# 16_-_PWR_2V5_1V5.net
KiCad netlist of a schematic drawn in Altium Designer
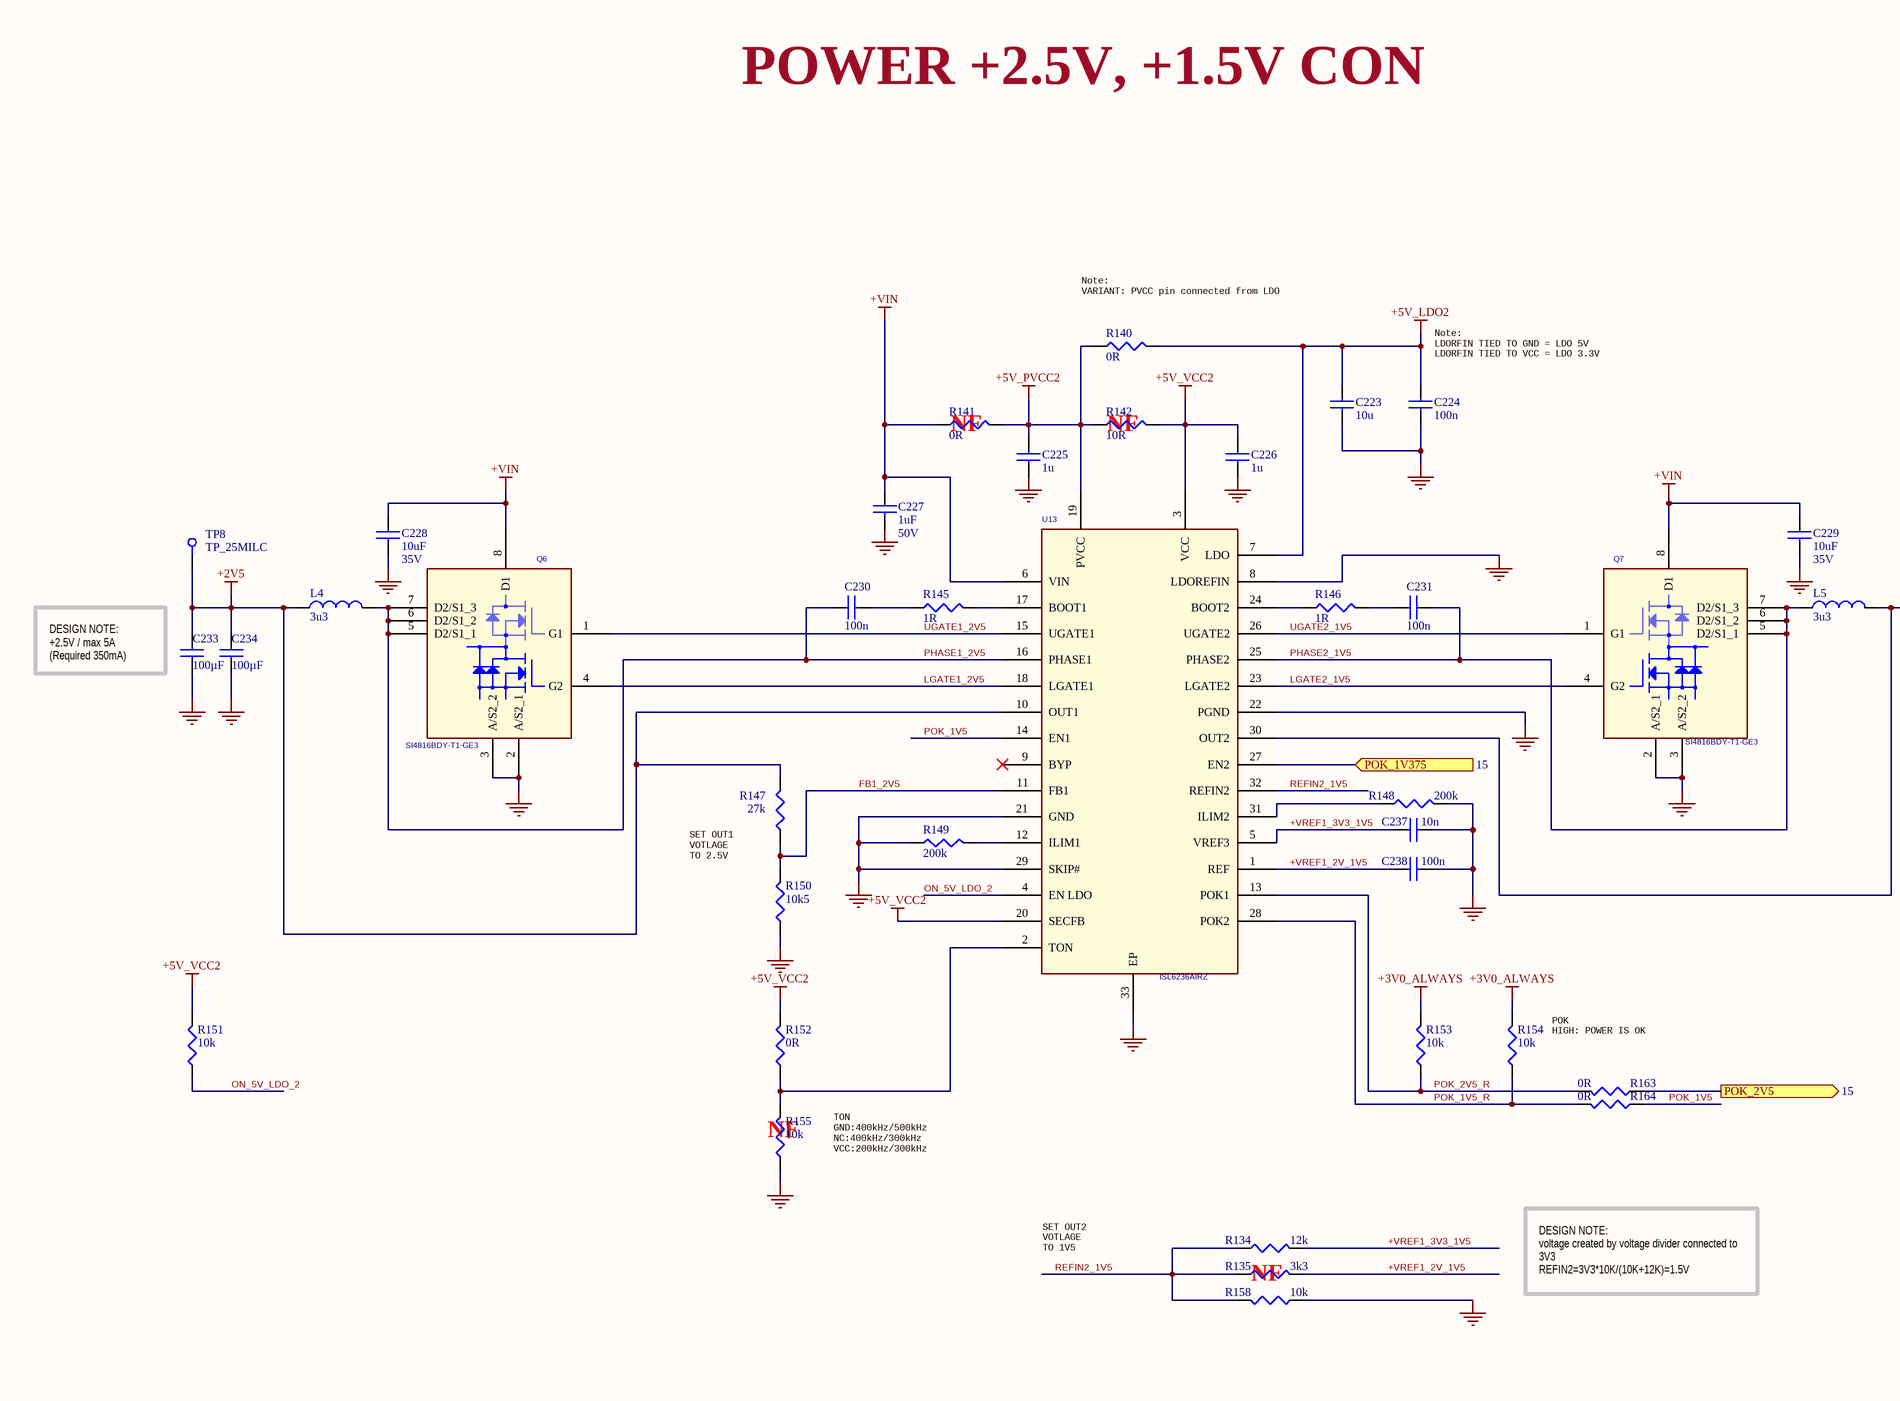
[diagram p0: [16] - PWR 2V5, 1V5.SchDoc, left]
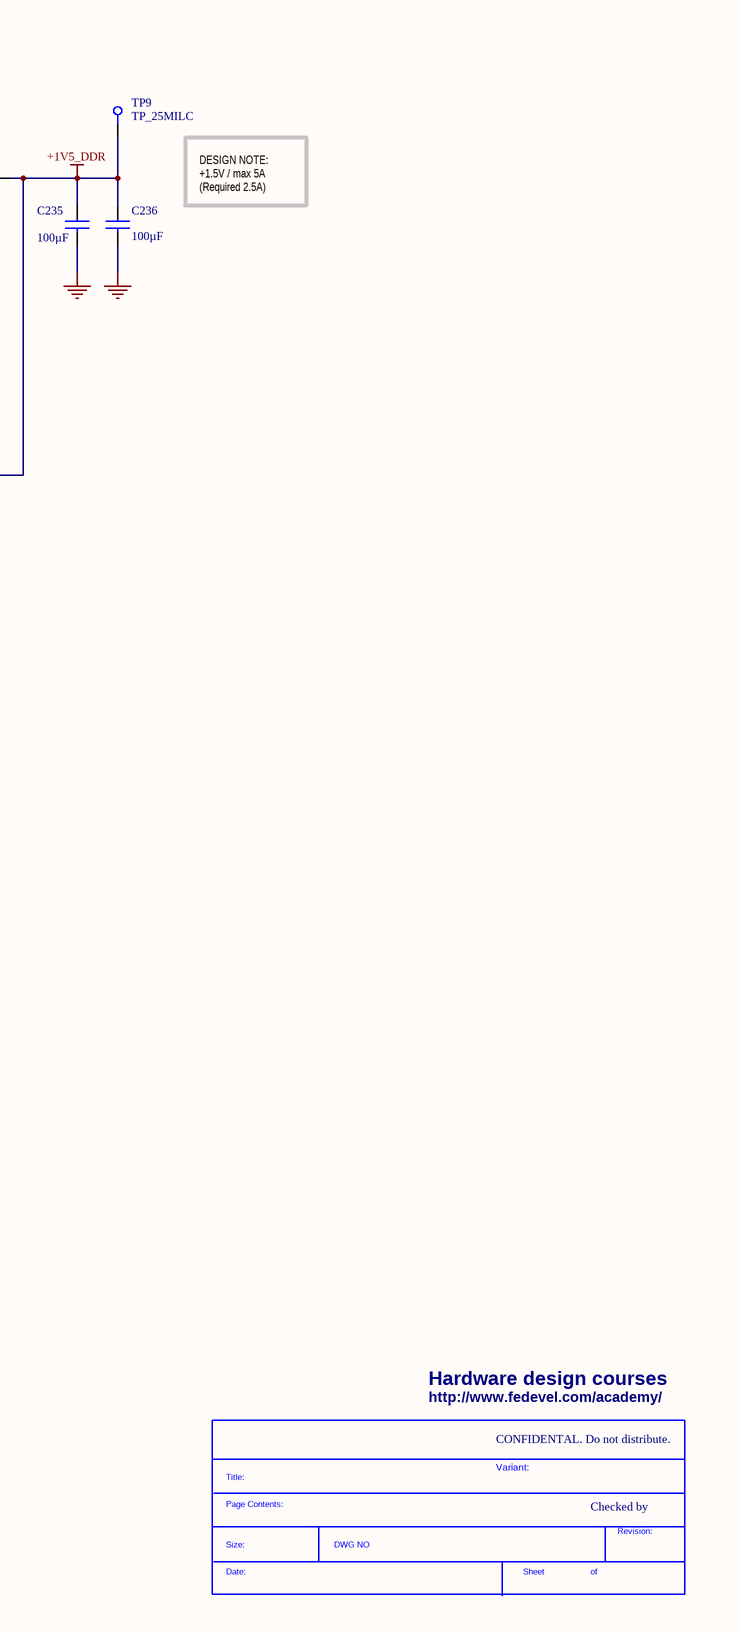
[diagram p1: [16] - PWR 2V5, 1V5.SchDoc, right]

(export (version "E")
  (design (tool "Eeschema 10.0.6"))
  (components
    (comp (ref "C223")
      (value "10u")
      (footprint "C0603")
      (description "CAP CER 10UF 6.3V X5R 20% 0603")
      (fields
        (field (name "MANUFACTURER") "TDK Corporation")
        (field (name "MANUFACTURER PART NUMBER") "C1608X5R0J106M")
      )
      (libsource (lib "Integrated_Library_RF_FEB_2012") (part "C1608X5R0J106M"))
    )
    (comp (ref "C224")
      (value "100n")
      (footprint "C0402")
      (description "CAP CER .10UF 50V X5R 10% 0402")
      (fields
        (field (name "MANUFACTURER") "TDK Corporation")
        (field (name "MANUFACTURER PART NUMBER") "C1005X5R1H104K")
      )
      (libsource (lib "Integrated_Library_RF_FEB_2012") (part "C1005X5R1H104K"))
    )
    (comp (ref "C225")
      (value "1u")
      (footprint "C0402")
      (description "CAP CER 1.0UF 16V X5R 0402")
      (fields
        (field (name "MANUFACTURER") "TDK Corporation")
        (field (name "MANUFACTURER PART NUMBER") "C1005X5R1C105K")
      )
      (libsource (lib "Integrated_Library_RF_FEB_2012") (part "C1005X5R1C105K"))
    )
    (comp (ref "C226")
      (value "1u")
      (footprint "C0402")
      (description "CAP CER 1.0UF 16V X5R 0402")
      (fields
        (field (name "MANUFACTURER") "TDK Corporation")
        (field (name "MANUFACTURER PART NUMBER") "C1005X5R1C105K")
      )
      (libsource (lib "Integrated_Library_RF_FEB_2012") (part "C1005X5R1C105K"))
    )
    (comp (ref "C227")
      (value "1uF")
      (footprint "C0805")
      (description "CAP CER 1UF 50V X7R 0805")
      (fields
        (field (name "MANUFACTURER") "Murata Electronics North America")
        (field (name "MANUFACTURER PART NUMBER") "GRM21BR71H105KA12L")
        (field (name "VOLTAGE - RATED") "50V")
      )
      (libsource (lib "Integrated_Library_RF_FEB_2012") (part "GRM21BR71H105KA12L"))
    )
    (comp (ref "C228")
      (value "10uF")
      (footprint "C1206")
      (description "CAP CER 10UF 35V X5R 1206")
      (fields
        (field (name "MANUFACTURER") "Murata Electronics North America")
        (field (name "MANUFACTURER PART NUMBER") "GRM31CR6YA106KA12L")
        (field (name "VOLTAGE - RATED") "35V")
      )
      (libsource (lib "Integrated_Library_RF_FEB_2012") (part "GRM31CR6YA106KA12L"))
    )
    (comp (ref "C229")
      (value "10uF")
      (footprint "C1206")
      (description "CAP CER 10UF 35V X5R 1206")
      (fields
        (field (name "MANUFACTURER") "Murata Electronics North America")
        (field (name "MANUFACTURER PART NUMBER") "GRM31CR6YA106KA12L")
        (field (name "VOLTAGE - RATED") "35V")
      )
      (libsource (lib "Integrated_Library_RF_FEB_2012") (part "GRM31CR6YA106KA12L"))
    )
    (comp (ref "C230")
      (value "100n")
      (footprint "C0402")
      (description "CAP CER .10UF 50V X5R 10% 0402")
      (fields
        (field (name "MANUFACTURER") "TDK Corporation")
        (field (name "MANUFACTURER PART NUMBER") "C1005X5R1H104K")
      )
      (libsource (lib "Integrated_Library_RF_FEB_2012") (part "C1005X5R1H104K"))
    )
    (comp (ref "C231")
      (value "100n")
      (footprint "C0402")
      (description "CAP CER .10UF 50V X5R 10% 0402")
      (fields
        (field (name "MANUFACTURER") "TDK Corporation")
        (field (name "MANUFACTURER PART NUMBER") "C1005X5R1H104K")
      )
      (libsource (lib "Integrated_Library_RF_FEB_2012") (part "C1005X5R1H104K"))
    )
    (comp (ref "C233")
      (value "100µF")
      (footprint "C1206")
      (description "CAP CER 100UF 10V X5R 20% 1206")
      (fields
        (field (name "MANUFACTURER") "TDK Corporation")
        (field (name "MANUFACTURER PART NUMBER") "C3216X5R1A107M")
      )
      (libsource (lib "Integrated_Library_RF_FEB_2012") (part "C3216X5R1A107M"))
    )
    (comp (ref "C234")
      (value "100µF")
      (footprint "C1206")
      (description "CAP CER 100UF 10V X5R 20% 1206")
      (fields
        (field (name "MANUFACTURER") "TDK Corporation")
        (field (name "MANUFACTURER PART NUMBER") "C3216X5R1A107M")
      )
      (libsource (lib "Integrated_Library_RF_FEB_2012") (part "C3216X5R1A107M"))
    )
    (comp (ref "C235")
      (value "100µF")
      (footprint "C1206")
      (description "CAP CER 100UF 10V X5R 20% 1206")
      (fields
        (field (name "MANUFACTURER") "TDK Corporation")
        (field (name "MANUFACTURER PART NUMBER") "C3216X5R1A107M")
      )
      (libsource (lib "Integrated_Library_RF_FEB_2012") (part "C3216X5R1A107M"))
    )
    (comp (ref "C236")
      (value "100µF")
      (footprint "C1206")
      (description "CAP CER 100UF 10V X5R 20% 1206")
      (fields
        (field (name "MANUFACTURER") "TDK Corporation")
        (field (name "MANUFACTURER PART NUMBER") "C3216X5R1A107M")
      )
      (libsource (lib "Integrated_Library_RF_FEB_2012") (part "C3216X5R1A107M"))
    )
    (comp (ref "C237")
      (value "10n")
      (footprint "C0402")
      (description "CAP CER 10000PF 16V X7R 10% 0402")
      (fields
        (field (name "MANUFACTURER") "TDK Corporation")
        (field (name "MANUFACTURER PART NUMBER") "C1005X7R1C103K")
      )
      (libsource (lib "Integrated_Library_RF_FEB_2012") (part "C1005X7R1C103K"))
    )
    (comp (ref "C238")
      (value "100n")
      (footprint "C0402")
      (description "CAP CER .10UF 50V X5R 10% 0402")
      (fields
        (field (name "MANUFACTURER") "TDK Corporation")
        (field (name "MANUFACTURER PART NUMBER") "C1005X5R1H104K")
      )
      (libsource (lib "Integrated_Library_RF_FEB_2012") (part "C1005X5R1H104K"))
    )
    (comp (ref "L4")
      (value "3u3")
      (footprint "IHLP_255MILx270MIL")
      (description "INDUCTOR POWER 3.3UH 6A SMD")
      (fields
        (field (name "MANUFACTURER") "Vishay Dale")
        (field (name "MANUFACTURER PART NUMBER") "IHLP2525CZER3R3M01")
        (field (name ".CHECKED PCB") "RF")
        (field (name ".CHECKED SCH") "RF")
      )
      (libsource (lib "Integrated_Library_RF_FEB_2012") (part "IHLP2525CZER3R3M01"))
    )
    (comp (ref "L5")
      (value "3u3")
      (footprint "IHLP_255MILx270MIL")
      (description "INDUCTOR POWER 3.3UH 6A SMD")
      (fields
        (field (name "MANUFACTURER") "Vishay Dale")
        (field (name "MANUFACTURER PART NUMBER") "IHLP2525CZER3R3M01")
        (field (name ".CHECKED PCB") "RF")
        (field (name ".CHECKED SCH") "RF")
      )
      (libsource (lib "Integrated_Library_RF_FEB_2012") (part "IHLP2525CZER3R3M01"))
    )
    (comp (ref "Q6")
      (value "SI4816BDY-T1-GE3")
      (footprint "8_SOIC_3.9MM")
      (description "MOSFET DL N-CH 30V 6.8A 8-SOIC")
      (fields (field (name "MANUFACTURER") "Vishay/Siliconix"))
      (libsource (lib "Integrated_Library_RF_FEB_2012") (part "SI4816BDY-T1-GE3"))
    )
    (comp (ref "Q7")
      (value "SI4816BDY-T1-GE3")
      (footprint "8_SOIC_3.9MM")
      (description "MOSFET DL N-CH 30V 6.8A 8-SOIC")
      (fields (field (name "MANUFACTURER") "Vishay/Siliconix"))
      (libsource (lib "Integrated_Library_RF_FEB_2012") (part "SI4816BDY-T1-GE3"))
    )
    (comp (ref "R134")
      (value "12k")
      (footprint "R0402")
      (description "RES 12.0K OHM 1/16W 1% 0402 SMD")
      (fields
        (field (name "MANUFACTURER") "Yageo")
        (field (name "MANUFACTURER PART NUMBER") "RC0402FR-0712KL")
      )
      (libsource (lib "Integrated_Library_RF_FEB_2012") (part "RC0402FR-0712KL"))
    )
    (comp (ref "R135")
      (value "3k3")
      (footprint "R0402")
      (description "RES 3.30K OHM 1/16W 1% 0402 SMD")
      (fields
        (field (name "MANUFACTURER") "Yageo")
        (field (name "MANUFACTURER PART NUMBER") "RC0402FR-073K3L")
      )
      (libsource (lib "Integrated_Library_RF_FEB_2012") (part "RC0402FR-073K3L"))
    )
    (comp (ref "R140")
      (value "0R")
      (footprint "R0402")
      (description "RES 0.0 OHM 1/16W 0402 SMD")
      (fields
        (field (name "MANUFACTURER") "Yageo")
        (field (name "MANUFACTURER PART NUMBER") "RC0402JR-070RL")
      )
      (libsource (lib "Integrated_Library_RF_FEB_2012") (part "RC0402JR-070RL"))
    )
    (comp (ref "R141")
      (value "0R")
      (footprint "R0402")
      (description "RES 0.0 OHM 1/16W 0402 SMD")
      (fields
        (field (name "MANUFACTURER") "Yageo")
        (field (name "MANUFACTURER PART NUMBER") "RC0402JR-070RL")
      )
      (libsource (lib "Integrated_Library_RF_FEB_2012") (part "RC0402JR-070RL"))
    )
    (comp (ref "R142")
      (value "10R")
      (footprint "R0402")
      (description "RES 10.0 OHM 1/16W 1% 0402 SMD")
      (fields
        (field (name "MANUFACTURER") "Yageo")
        (field (name "MANUFACTURER PART NUMBER") "RC0402FR-0710RL")
      )
      (libsource (lib "Integrated_Library_RF_FEB_2012") (part "RC0402FR-0710RL"))
    )
    (comp (ref "R145")
      (value "1R")
      (footprint "R0402")
      (description "RES 1.00 OHM 1/16W 1% 0402 SM")
      (fields
        (field (name "MANUFACTURER") "Yageo")
        (field (name "MANUFACTURER PART NUMBER") "RC0402FR-071RL")
      )
      (libsource (lib "Integrated_Library_RF_FEB_2012") (part "RC0402FR-071RL"))
    )
    (comp (ref "R146")
      (value "1R")
      (footprint "R0402")
      (description "RES 1.00 OHM 1/16W 1% 0402 SM")
      (fields
        (field (name "MANUFACTURER") "Yageo")
        (field (name "MANUFACTURER PART NUMBER") "RC0402FR-071RL")
      )
      (libsource (lib "Integrated_Library_RF_FEB_2012") (part "RC0402FR-071RL"))
    )
    (comp (ref "R147")
      (value "27k")
      (footprint "R0402")
      (description "RES 27.0K OHM 1/16W 1% 0402 SMD")
      (fields
        (field (name "MANUFACTURER") "Yageo")
        (field (name "MANUFACTURER PART NUMBER") "RC0402FR-0727KL")
        (field (name ".CHECKED PCB") "RF")
        (field (name ".CHECKED SCH") "RF")
      )
      (libsource (lib "Integrated_Library_RF_FEB_2012") (part "RC0402FR-0727KL"))
    )
    (comp (ref "R148")
      (value "200k")
      (footprint "R0402")
      (description "RES 200K OHM 1/16W 1% 0402 SMD")
      (fields
        (field (name "MANUFACTURER") "Yageo")
        (field (name "MANUFACTURER PART NUMBER") "RC0402FR-07200KL")
      )
      (libsource (lib "Integrated_Library_RF_FEB_2012") (part "RC0402FR-07200KL"))
    )
    (comp (ref "R149")
      (value "200k")
      (footprint "R0402")
      (description "RES 200K OHM 1/16W 1% 0402 SMD")
      (fields
        (field (name "MANUFACTURER") "Yageo")
        (field (name "MANUFACTURER PART NUMBER") "RC0402FR-07200KL")
      )
      (libsource (lib "Integrated_Library_RF_FEB_2012") (part "RC0402FR-07200KL"))
    )
    (comp (ref "R150")
      (value "10k5")
      (footprint "R0402")
      (description "RES 10.5K OHM 1/16W 1% 0402 SMD")
      (fields
        (field (name "MANUFACTURER") "Vishay/Dale")
        (field (name "MANUFACTURER PART NUMBER") "CRCW040210K5FKED")
      )
      (libsource (lib "Integrated_Library_RF_FEB_2012") (part "CRCW040210K5FKED"))
    )
    (comp (ref "R151")
      (value "10k")
      (footprint "R0402")
      (description "RES 10.0K OHM 1/16W 1% 0402 SMD")
      (fields
        (field (name "MANUFACTURER") "Yageo")
        (field (name "MANUFACTURER PART NUMBER") "RC0402FR-0710KL")
      )
      (libsource (lib "Integrated_Library_RF_FEB_2012") (part "RC0402FR-0710KL"))
    )
    (comp (ref "R152")
      (value "0R")
      (footprint "R0402")
      (description "RES 0.0 OHM 1/16W 0402 SMD")
      (fields
        (field (name "MANUFACTURER") "Yageo")
        (field (name "MANUFACTURER PART NUMBER") "RC0402JR-070RL")
      )
      (libsource (lib "Integrated_Library_RF_FEB_2012") (part "RC0402JR-070RL"))
    )
    (comp (ref "R153")
      (value "10k")
      (footprint "R0402")
      (description "RES 10.0K OHM 1/16W 1% 0402 SMD")
      (fields
        (field (name "MANUFACTURER") "Yageo")
        (field (name "MANUFACTURER PART NUMBER") "RC0402FR-0710KL")
      )
      (libsource (lib "Integrated_Library_RF_FEB_2012") (part "RC0402FR-0710KL"))
    )
    (comp (ref "R154")
      (value "10k")
      (footprint "R0402")
      (description "RES 10.0K OHM 1/16W 1% 0402 SMD")
      (fields
        (field (name "MANUFACTURER") "Yageo")
        (field (name "MANUFACTURER PART NUMBER") "RC0402FR-0710KL")
      )
      (libsource (lib "Integrated_Library_RF_FEB_2012") (part "RC0402FR-0710KL"))
    )
    (comp (ref "R155")
      (value "10k")
      (footprint "R0402")
      (description "RES 10.0K OHM 1/16W 1% 0402 SMD")
      (fields
        (field (name "MANUFACTURER") "Yageo")
        (field (name "MANUFACTURER PART NUMBER") "RC0402FR-0710KL")
      )
      (libsource (lib "Integrated_Library_RF_FEB_2012") (part "RC0402FR-0710KL"))
    )
    (comp (ref "R158")
      (value "10k")
      (footprint "R0402")
      (description "RES 10.0K OHM 1/16W 1% 0402 SMD")
      (fields
        (field (name "MANUFACTURER") "Yageo")
        (field (name "MANUFACTURER PART NUMBER") "RC0402FR-0710KL")
      )
      (libsource (lib "Integrated_Library_RF_FEB_2012") (part "RC0402FR-0710KL"))
    )
    (comp (ref "R163")
      (value "0R")
      (footprint "R0402")
      (description "RES 0.0 OHM 1/16W 0402 SMD")
      (fields
        (field (name "MANUFACTURER") "Yageo")
        (field (name "MANUFACTURER PART NUMBER") "RC0402JR-070RL")
      )
      (libsource (lib "Integrated_Library_RF_FEB_2012") (part "RC0402JR-070RL"))
    )
    (comp (ref "R164")
      (value "0R")
      (footprint "R0402")
      (description "RES 0.0 OHM 1/16W 0402 SMD")
      (fields
        (field (name "MANUFACTURER") "Yageo")
        (field (name "MANUFACTURER PART NUMBER") "RC0402JR-070RL")
      )
      (libsource (lib "Integrated_Library_RF_FEB_2012") (part "RC0402JR-070RL"))
    )
    (comp (ref "TP8")
      (value "TP_25MILC")
      (footprint "TP_25C")
      (description "Test Point 25mil")
      (libsource (lib "Integrated_Library_RF_FEB_2012") (part "TP_25MILC"))
    )
    (comp (ref "TP9")
      (value "TP_25MILC")
      (footprint "TP_25C")
      (description "Test Point 25mil")
      (libsource (lib "Integrated_Library_RF_FEB_2012") (part "TP_25MILC"))
    )
    (comp (ref "U13")
      (value "ISL6236AIRZ")
      (footprint "32_VFQFN_EXPOSED_PAD")
      (description "IC MAIN PWR CTRLR QUAD 32-QFN")
      (fields (field (name "MANUFACTURER") "Intersil"))
      (libsource (lib "Integrated_Library_RF_FEB_2012") (part "ISL6236AIRZ"))
    )
  )
  (nets
    (net (code "1") (name "+1V5_DDR") (class "Default")
      (node (ref "C235") (pin "1") (pinfunction "1_1") (pintype "passive"))
      (node (ref "C236") (pin "1") (pinfunction "1_1") (pintype "passive"))
      (node (ref "L5") (pin "2") (pinfunction "2_2") (pintype "passive"))
      (node (ref "TP9") (pin "1") (pinfunction "1_1") (pintype "passive"))
      (node (ref "U13") (pin "30") (pinfunction "OUT2_30") (pintype "passive"))
    )
    (net (code "2") (name "+2V5") (class "Default")
      (node (ref "C233") (pin "1") (pinfunction "1_1") (pintype "passive"))
      (node (ref "C234") (pin "1") (pinfunction "1_1") (pintype "passive"))
      (node (ref "L4") (pin "1") (pinfunction "1_1") (pintype "passive"))
      (node (ref "R147") (pin "2") (pinfunction "2_2") (pintype "passive"))
      (node (ref "TP8") (pin "1") (pinfunction "1_1") (pintype "passive"))
      (node (ref "U13") (pin "10") (pinfunction "OUT1_10") (pintype "passive"))
    )
    (net (code "3") (name "+3V0_ALWAYS") (class "Default")
      (node (ref "R153") (pin "2") (pinfunction "2_2") (pintype "passive"))
      (node (ref "R154") (pin "2") (pinfunction "2_2") (pintype "passive"))
    )
    (net (code "4") (name "+5V_LDO2") (class "Default")
      (node (ref "C223") (pin "1") (pinfunction "1_1") (pintype "passive"))
      (node (ref "C224") (pin "1") (pinfunction "1_1") (pintype "passive"))
      (node (ref "R140") (pin "2") (pinfunction "2_2") (pintype "passive"))
      (node (ref "U13") (pin "7") (pinfunction "LDO_7") (pintype "passive"))
    )
    (net (code "5") (name "+5V_PVCC2") (class "Default")
      (node (ref "C225") (pin "1") (pinfunction "1_1") (pintype "passive"))
      (node (ref "R140") (pin "1") (pinfunction "1_1") (pintype "passive"))
      (node (ref "R141") (pin "2") (pinfunction "2_2") (pintype "passive"))
      (node (ref "R142") (pin "1") (pinfunction "1_1") (pintype "passive"))
      (node (ref "U13") (pin "19") (pinfunction "PVCC_19") (pintype "passive"))
    )
    (net (code "6") (name "+5V_VCC2") (class "Default")
      (node (ref "C226") (pin "1") (pinfunction "1_1") (pintype "passive"))
      (node (ref "R142") (pin "2") (pinfunction "2_2") (pintype "passive"))
      (node (ref "R151") (pin "2") (pinfunction "2_2") (pintype "passive"))
      (node (ref "R152") (pin "2") (pinfunction "2_2") (pintype "passive"))
      (node (ref "U13") (pin "20") (pinfunction "SECFB_20") (pintype "passive"))
      (node (ref "U13") (pin "3") (pinfunction "VCC_3") (pintype "passive"))
    )
    (net (code "7") (name "+VIN") (class "Default")
      (node (ref "C227") (pin "1") (pinfunction "1_1") (pintype "passive"))
      (node (ref "C228") (pin "1") (pinfunction "1_1") (pintype "passive"))
      (node (ref "C229") (pin "1") (pinfunction "1_1") (pintype "passive"))
      (node (ref "Q6") (pin "8") (pinfunction "D1_8") (pintype "passive"))
      (node (ref "Q7") (pin "8") (pinfunction "D1_8") (pintype "passive"))
      (node (ref "R141") (pin "1") (pinfunction "1_1") (pintype "passive"))
      (node (ref "U13") (pin "6") (pinfunction "VIN_6") (pintype "passive"))
    )
    (net (code "8") (name "/+VREF1_2V_1V5") (class "Default")
      (node (ref "C238") (pin "1") (pinfunction "1_1") (pintype "passive"))
      (node (ref "R135") (pin "2") (pinfunction "2_2") (pintype "passive"))
      (node (ref "U13") (pin "1") (pinfunction "REF_1") (pintype "passive"))
    )
    (net (code "9") (name "/+VREF1_3V3_1V5") (class "Default")
      (node (ref "C237") (pin "1") (pinfunction "1_1") (pintype "passive"))
      (node (ref "R134") (pin "2") (pinfunction "2_2") (pintype "passive"))
      (node (ref "U13") (pin "5") (pinfunction "VREF3_5") (pintype "passive"))
    )
    (net (code "10") (name "/FB1_2V5") (class "Default")
      (node (ref "R147") (pin "1") (pinfunction "1_1") (pintype "passive"))
      (node (ref "R150") (pin "2") (pinfunction "2_2") (pintype "passive"))
      (node (ref "U13") (pin "11") (pinfunction "FB1_11") (pintype "passive"))
    )
    (net (code "11") (name "/LGATE1_2V5") (class "Default")
      (node (ref "Q6") (pin "4") (pinfunction "G2_4") (pintype "passive"))
      (node (ref "U13") (pin "18") (pinfunction "LGATE1_18") (pintype "passive"))
    )
    (net (code "12") (name "/LGATE2_1V5") (class "Default")
      (node (ref "Q7") (pin "4") (pinfunction "G2_4") (pintype "passive"))
      (node (ref "U13") (pin "23") (pinfunction "LGATE2_23") (pintype "passive"))
    )
    (net (code "13") (name "/ON_5V_LDO_2") (class "Default")
      (node (ref "R151") (pin "1") (pinfunction "1_1") (pintype "passive"))
      (node (ref "U13") (pin "4") (pinfunction "EN_LDO_4") (pintype "passive"))
    )
    (net (code "14") (name "/PHASE1_2V5") (class "Default")
      (node (ref "C230") (pin "1") (pinfunction "1_1") (pintype "passive"))
      (node (ref "L4") (pin "2") (pinfunction "2_2") (pintype "passive"))
      (node (ref "Q6") (pin "5") (pinfunction "D2/S1_1_5") (pintype "passive"))
      (node (ref "Q6") (pin "6") (pinfunction "D2/S1_2_6") (pintype "passive"))
      (node (ref "Q6") (pin "7") (pinfunction "D2/S1_3_7") (pintype "passive"))
      (node (ref "U13") (pin "16") (pinfunction "PHASE1_16") (pintype "passive"))
    )
    (net (code "15") (name "/PHASE2_1V5") (class "Default")
      (node (ref "C231") (pin "2") (pinfunction "2_2") (pintype "passive"))
      (node (ref "L5") (pin "1") (pinfunction "1_1") (pintype "passive"))
      (node (ref "Q7") (pin "5") (pinfunction "D2/S1_1_5") (pintype "passive"))
      (node (ref "Q7") (pin "6") (pinfunction "D2/S1_2_6") (pintype "passive"))
      (node (ref "Q7") (pin "7") (pinfunction "D2/S1_3_7") (pintype "passive"))
      (node (ref "U13") (pin "25") (pinfunction "PHASE2_25") (pintype "passive"))
    )
    (net (code "16") (name "/POK_1V5") (class "Default")
      (node (ref "R164") (pin "1") (pinfunction "1_1") (pintype "passive"))
      (node (ref "U13") (pin "14") (pinfunction "EN1_14") (pintype "passive"))
    )
    (net (code "17") (name "/POK_1V5_R") (class "Default")
      (node (ref "R154") (pin "1") (pinfunction "1_1") (pintype "passive"))
      (node (ref "R164") (pin "2") (pinfunction "2_2") (pintype "passive"))
      (node (ref "U13") (pin "28") (pinfunction "POK2_28") (pintype "passive"))
    )
    (net (code "18") (name "/POK_1V375") (class "Default")
      (node (ref "U13") (pin "27") (pinfunction "EN2_27") (pintype "passive"))
    )
    (net (code "19") (name "/POK_2V5") (class "Default")
      (node (ref "R163") (pin "1") (pinfunction "1_1") (pintype "passive"))
    )
    (net (code "20") (name "/POK_2V5_R") (class "Default")
      (node (ref "R153") (pin "1") (pinfunction "1_1") (pintype "passive"))
      (node (ref "R163") (pin "2") (pinfunction "2_2") (pintype "passive"))
      (node (ref "U13") (pin "13") (pinfunction "POK1_13") (pintype "passive"))
    )
    (net (code "21") (name "/REFIN2_1V5") (class "Default")
      (node (ref "R134") (pin "1") (pinfunction "1_1") (pintype "passive"))
      (node (ref "R135") (pin "1") (pinfunction "1_1") (pintype "passive"))
      (node (ref "R158") (pin "2") (pinfunction "2_2") (pintype "passive"))
      (node (ref "U13") (pin "32") (pinfunction "REFIN2_32") (pintype "passive"))
    )
    (net (code "22") (name "/UGATE1_2V5") (class "Default")
      (node (ref "Q6") (pin "1") (pinfunction "G1_1") (pintype "passive"))
      (node (ref "U13") (pin "15") (pinfunction "UGATE1_15") (pintype "passive"))
    )
    (net (code "23") (name "/UGATE2_1V5") (class "Default")
      (node (ref "Q7") (pin "1") (pinfunction "G1_1") (pintype "passive"))
      (node (ref "U13") (pin "26") (pinfunction "UGATE2_26") (pintype "passive"))
    )
    (net (code "24") (name "GND") (class "Default")
      (node (ref "C223") (pin "2") (pinfunction "2_2") (pintype "passive"))
      (node (ref "C224") (pin "2") (pinfunction "2_2") (pintype "passive"))
      (node (ref "C225") (pin "2") (pinfunction "2_2") (pintype "passive"))
      (node (ref "C226") (pin "2") (pinfunction "2_2") (pintype "passive"))
      (node (ref "C227") (pin "2") (pinfunction "2_2") (pintype "passive"))
      (node (ref "C228") (pin "2") (pinfunction "2_2") (pintype "passive"))
      (node (ref "C229") (pin "2") (pinfunction "2_2") (pintype "passive"))
      (node (ref "C233") (pin "2") (pinfunction "2_2") (pintype "passive"))
      (node (ref "C234") (pin "2") (pinfunction "2_2") (pintype "passive"))
      (node (ref "C235") (pin "2") (pinfunction "2_2") (pintype "passive"))
      (node (ref "C236") (pin "2") (pinfunction "2_2") (pintype "passive"))
      (node (ref "C237") (pin "2") (pinfunction "2_2") (pintype "passive"))
      (node (ref "C238") (pin "2") (pinfunction "2_2") (pintype "passive"))
      (node (ref "Q6") (pin "2") (pinfunction "A/S2_1_2") (pintype "passive"))
      (node (ref "Q6") (pin "3") (pinfunction "A/S2_2_3") (pintype "passive"))
      (node (ref "Q7") (pin "2") (pinfunction "A/S2_1_2") (pintype "passive"))
      (node (ref "Q7") (pin "3") (pinfunction "A/S2_2_3") (pintype "passive"))
      (node (ref "R148") (pin "2") (pinfunction "2_2") (pintype "passive"))
      (node (ref "R149") (pin "1") (pinfunction "1_1") (pintype "passive"))
      (node (ref "R150") (pin "1") (pinfunction "1_1") (pintype "passive"))
      (node (ref "R155") (pin "1") (pinfunction "1_1") (pintype "passive"))
      (node (ref "R158") (pin "1") (pinfunction "1_1") (pintype "passive"))
      (node (ref "U13") (pin "21") (pinfunction "GND_21") (pintype "passive"))
      (node (ref "U13") (pin "22") (pinfunction "PGND_22") (pintype "passive"))
      (node (ref "U13") (pin "29") (pinfunction "SKIP#_29") (pintype "passive"))
      (node (ref "U13") (pin "33") (pinfunction "EP_33") (pintype "passive"))
      (node (ref "U13") (pin "8") (pinfunction "LDOREFIN_8") (pintype "passive"))
    )
    (net (code "25") (name "Net-(C230-Pad2)") (class "Default")
      (node (ref "C230") (pin "2") (pinfunction "2_2") (pintype "passive"))
      (node (ref "R145") (pin "1") (pinfunction "1_1") (pintype "passive"))
    )
    (net (code "26") (name "Net-(C231-Pad1)") (class "Default")
      (node (ref "C231") (pin "1") (pinfunction "1_1") (pintype "passive"))
      (node (ref "R146") (pin "2") (pinfunction "2_2") (pintype "passive"))
    )
    (net (code "27") (name "Net-(U13-BOOT1)") (class "Default")
      (node (ref "R145") (pin "2") (pinfunction "2_2") (pintype "passive"))
      (node (ref "U13") (pin "17") (pinfunction "BOOT1_17") (pintype "passive"))
    )
    (net (code "28") (name "Net-(U13-BOOT2)") (class "Default")
      (node (ref "R146") (pin "1") (pinfunction "1_1") (pintype "passive"))
      (node (ref "U13") (pin "24") (pinfunction "BOOT2_24") (pintype "passive"))
    )
    (net (code "29") (name "Net-(U13-ILIM1)") (class "Default")
      (node (ref "R149") (pin "2") (pinfunction "2_2") (pintype "passive"))
      (node (ref "U13") (pin "12") (pinfunction "ILIM1_12") (pintype "passive"))
    )
    (net (code "30") (name "Net-(U13-ILIM2)") (class "Default")
      (node (ref "R148") (pin "1") (pinfunction "1_1") (pintype "passive"))
      (node (ref "U13") (pin "31") (pinfunction "ILIM2_31") (pintype "passive"))
    )
    (net (code "31") (name "Net-(U13-TON)") (class "Default")
      (node (ref "R152") (pin "1") (pinfunction "1_1") (pintype "passive"))
      (node (ref "R155") (pin "2") (pinfunction "2_2") (pintype "passive"))
      (node (ref "U13") (pin "2") (pinfunction "TON_2") (pintype "passive"))
    )
    (net (code "32") (name "unconnected-(U13-BYP-Pad9)") (class "Default")
      (node (ref "U13") (pin "9") (pinfunction "BYP_9") (pintype "passive+no_connect"))
    )
  )
)
